# main_V3.net
KiCad netlist of a schematic drawn in EAGLE
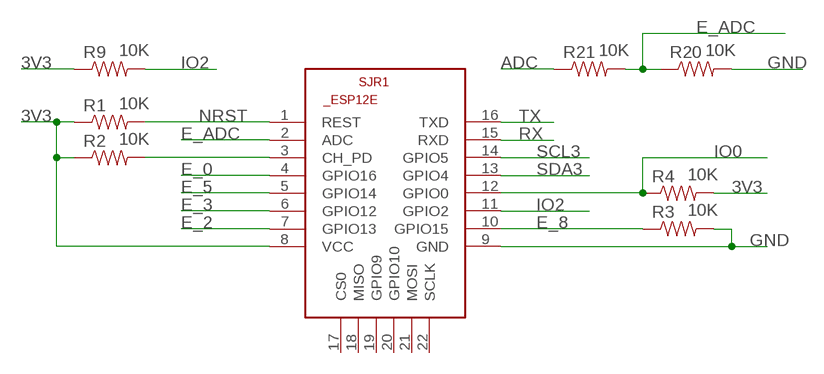
[diagram p0: schematic, sheet 1]
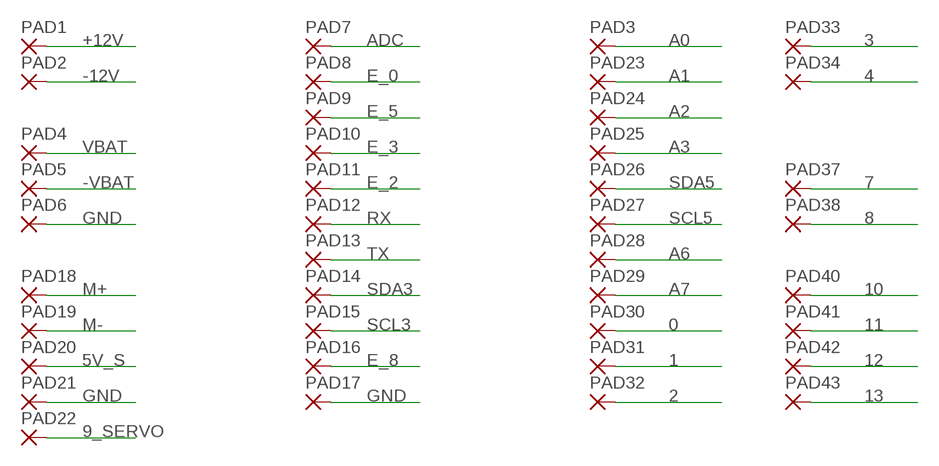
[diagram p1: schematic, sheet 2]
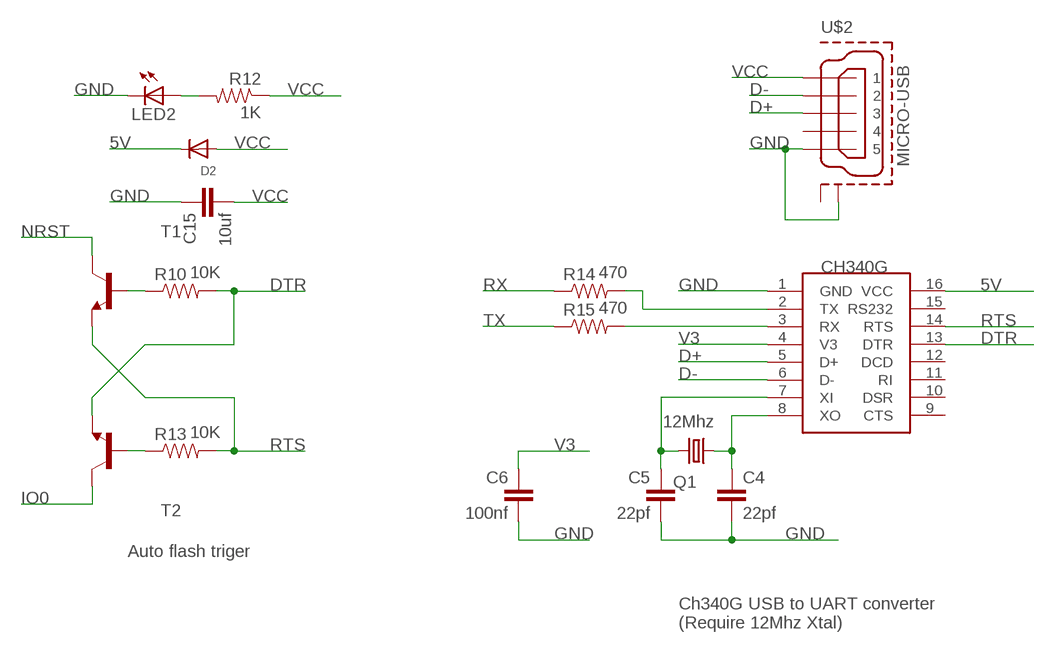
[diagram p2: schematic, sheet 3]
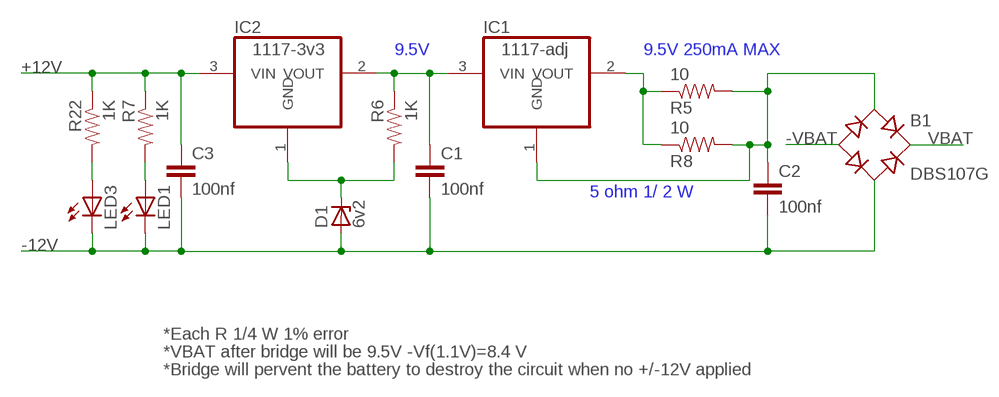
[diagram p3: schematic, sheet 4]
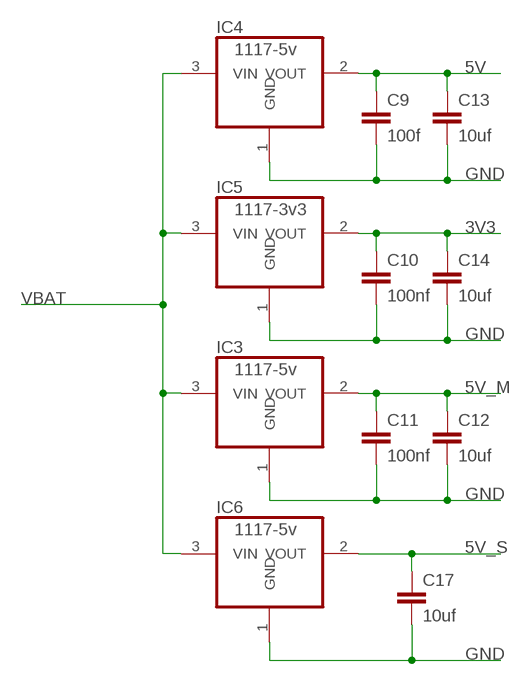
[diagram p4: schematic, sheet 5]
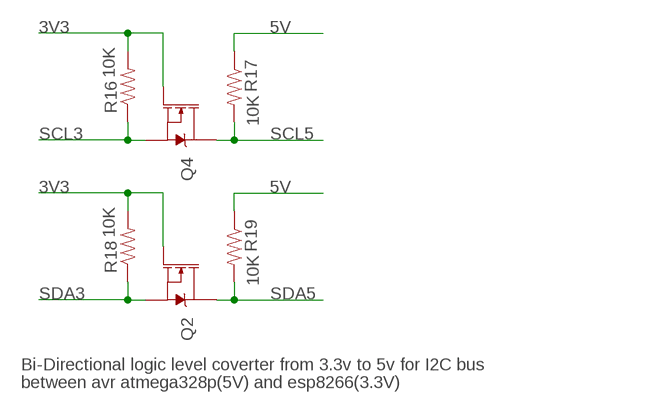
[diagram p5: schematic, sheet 6]
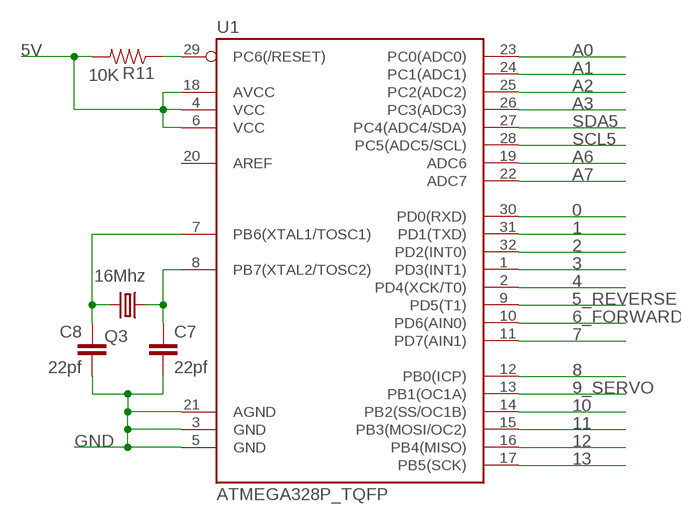
[diagram p6: schematic, sheet 7]
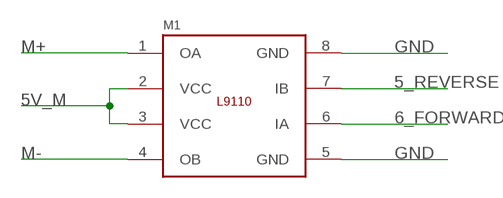
[diagram p7: schematic, sheet 8]

(export (version "E")
  (design (tool "Eeschema 10.0.6"))
  (components
    (comp (ref "Q2")
      (value "MOSFET-NCH-BSS138")
      (footprint "eagle-import:SOT23-3")
      (libsource (lib "eagle-import") (part "MOSFET-NCH-BSS138"))
    )
    (comp (ref "Q4")
      (value "MOSFET-NCH-BSS138")
      (footprint "eagle-import:SOT23-3")
      (libsource (lib "eagle-import") (part "MOSFET-NCH-BSS138"))
    )
    (comp (ref "R16")
      (value "10K")
      (footprint "eagle-import:1206")
      (libsource (lib "eagle-import") (part "RESISTOR1206"))
    )
    (comp (ref "R17")
      (value "10K")
      (footprint "eagle-import:1206")
      (libsource (lib "eagle-import") (part "RESISTOR1206"))
    )
    (comp (ref "R18")
      (value "10K")
      (footprint "eagle-import:1206")
      (libsource (lib "eagle-import") (part "RESISTOR1206"))
    )
    (comp (ref "R19")
      (value "10K")
      (footprint "eagle-import:1206")
      (libsource (lib "eagle-import") (part "RESISTOR1206"))
    )
    (comp (ref "B1")
      (value "DBS107G")
      (footprint "eagle-import:DBS")
      (libsource (lib "eagle-import") (part "DB?GS107"))
    )
    (comp (ref "C1")
      (value "100nf")
      (footprint "eagle-import:C1206K")
      (libsource (lib "eagle-import") (part "C-EUC1206K"))
    )
    (comp (ref "C2")
      (value "100nf")
      (footprint "eagle-import:C1206K")
      (libsource (lib "eagle-import") (part "C-EUC1206K"))
    )
    (comp (ref "C3")
      (value "100nf")
      (footprint "eagle-import:C1206K")
      (libsource (lib "eagle-import") (part "C-EUC1206K"))
    )
    (comp (ref "D1")
      (value "6v2")
      (footprint "eagle-import:SOT23")
      (libsource (lib "eagle-import") (part "ZENER-DIODESOT23"))
    )
    (comp (ref "IC1")
      (value "1117-adj")
      (footprint "eagle-import:SOT223")
      (fields (field (name "MPN") "REG1117"))
      (libsource (lib "eagle-import") (part "REG1117"))
    )
    (comp (ref "IC2")
      (value "1117-3v3")
      (footprint "eagle-import:SOT223")
      (fields (field (name "MPN") "REG1117"))
      (libsource (lib "eagle-import") (part "REG1117"))
    )
    (comp (ref "LED1")
      (value "LEDSMT1206")
      (footprint "eagle-import:1206")
      (libsource (lib "eagle-import") (part "LEDSMT1206"))
    )
    (comp (ref "LED3")
      (value "LEDSMT1206")
      (footprint "eagle-import:1206")
      (libsource (lib "eagle-import") (part "LEDSMT1206"))
    )
    (comp (ref "R5")
      (value "10")
      (footprint "eagle-import:1206")
      (libsource (lib "eagle-import") (part "RESISTOR1206"))
    )
    (comp (ref "R6")
      (value "1K")
      (footprint "eagle-import:1206")
      (libsource (lib "eagle-import") (part "RESISTOR1206"))
    )
    (comp (ref "R7")
      (value "1K")
      (footprint "eagle-import:1206")
      (libsource (lib "eagle-import") (part "RESISTOR1206"))
    )
    (comp (ref "R8")
      (value "10")
      (footprint "eagle-import:1206")
      (libsource (lib "eagle-import") (part "RESISTOR1206"))
    )
    (comp (ref "R22")
      (value "1K")
      (footprint "eagle-import:1206")
      (libsource (lib "eagle-import") (part "RESISTOR1206"))
    )
    (comp (ref "PAD1")
      (value "WIREPADSMD5-2,5")
      (footprint "eagle-import:5-2,5")
      (libsource (lib "eagle-import") (part "WIREPADSMD5-2,5"))
    )
    (comp (ref "PAD2")
      (value "WIREPADSMD5-2,5")
      (footprint "eagle-import:5-2,5")
      (libsource (lib "eagle-import") (part "WIREPADSMD5-2,5"))
    )
    (comp (ref "PAD3")
      (value "WIREPADSMD1,27-254")
      (footprint "eagle-import:SMD1,27-2,54")
      (libsource (lib "eagle-import") (part "WIREPADSMD1,27-254"))
    )
    (comp (ref "PAD4")
      (value "WIREPADSMD5-2,5")
      (footprint "eagle-import:5-2,5")
      (libsource (lib "eagle-import") (part "WIREPADSMD5-2,5"))
    )
    (comp (ref "PAD5")
      (value "WIREPADSMD5-2,5")
      (footprint "eagle-import:5-2,5")
      (libsource (lib "eagle-import") (part "WIREPADSMD5-2,5"))
    )
    (comp (ref "PAD6")
      (value "WIREPADSMD5-2,5")
      (footprint "eagle-import:5-2,5")
      (libsource (lib "eagle-import") (part "WIREPADSMD5-2,5"))
    )
    (comp (ref "PAD7")
      (value "WIREPADSMD1,27-254")
      (footprint "eagle-import:SMD1,27-2,54")
      (libsource (lib "eagle-import") (part "WIREPADSMD1,27-254"))
    )
    (comp (ref "PAD8")
      (value "WIREPADSMD1,27-254")
      (footprint "eagle-import:SMD1,27-2,54")
      (libsource (lib "eagle-import") (part "WIREPADSMD1,27-254"))
    )
    (comp (ref "PAD9")
      (value "WIREPADSMD1,27-254")
      (footprint "eagle-import:SMD1,27-2,54")
      (libsource (lib "eagle-import") (part "WIREPADSMD1,27-254"))
    )
    (comp (ref "PAD10")
      (value "WIREPADSMD1,27-254")
      (footprint "eagle-import:SMD1,27-2,54")
      (libsource (lib "eagle-import") (part "WIREPADSMD1,27-254"))
    )
    (comp (ref "PAD11")
      (value "WIREPADSMD1,27-254")
      (footprint "eagle-import:SMD1,27-2,54")
      (libsource (lib "eagle-import") (part "WIREPADSMD1,27-254"))
    )
    (comp (ref "PAD12")
      (value "WIREPADSMD1,27-254")
      (footprint "eagle-import:SMD1,27-2,54")
      (libsource (lib "eagle-import") (part "WIREPADSMD1,27-254"))
    )
    (comp (ref "PAD13")
      (value "WIREPADSMD1,27-254")
      (footprint "eagle-import:SMD1,27-2,54")
      (libsource (lib "eagle-import") (part "WIREPADSMD1,27-254"))
    )
    (comp (ref "PAD14")
      (value "WIREPADSMD1,27-254")
      (footprint "eagle-import:SMD1,27-2,54")
      (libsource (lib "eagle-import") (part "WIREPADSMD1,27-254"))
    )
    (comp (ref "PAD15")
      (value "WIREPADSMD1,27-254")
      (footprint "eagle-import:SMD1,27-2,54")
      (libsource (lib "eagle-import") (part "WIREPADSMD1,27-254"))
    )
    (comp (ref "PAD16")
      (value "WIREPADSMD1,27-254")
      (footprint "eagle-import:SMD1,27-2,54")
      (libsource (lib "eagle-import") (part "WIREPADSMD1,27-254"))
    )
    (comp (ref "PAD17")
      (value "WIREPADSMD1,27-254")
      (footprint "eagle-import:SMD1,27-2,54")
      (libsource (lib "eagle-import") (part "WIREPADSMD1,27-254"))
    )
    (comp (ref "PAD18")
      (value "WIREPADSMD1,27-254")
      (footprint "eagle-import:SMD1,27-2,54")
      (libsource (lib "eagle-import") (part "WIREPADSMD1,27-254"))
    )
    (comp (ref "PAD19")
      (value "WIREPADSMD1,27-254")
      (footprint "eagle-import:SMD1,27-2,54")
      (libsource (lib "eagle-import") (part "WIREPADSMD1,27-254"))
    )
    (comp (ref "PAD20")
      (value "WIREPADSMD1,27-254")
      (footprint "eagle-import:SMD1,27-2,54")
      (libsource (lib "eagle-import") (part "WIREPADSMD1,27-254"))
    )
    (comp (ref "PAD21")
      (value "WIREPADSMD1,27-254")
      (footprint "eagle-import:SMD1,27-2,54")
      (libsource (lib "eagle-import") (part "WIREPADSMD1,27-254"))
    )
    (comp (ref "PAD22")
      (value "WIREPADSMD1,27-254")
      (footprint "eagle-import:SMD1,27-2,54")
      (libsource (lib "eagle-import") (part "WIREPADSMD1,27-254"))
    )
    (comp (ref "PAD23")
      (value "WIREPADSMD1,27-254")
      (footprint "eagle-import:SMD1,27-2,54")
      (libsource (lib "eagle-import") (part "WIREPADSMD1,27-254"))
    )
    (comp (ref "PAD24")
      (value "WIREPADSMD1,27-254")
      (footprint "eagle-import:SMD1,27-2,54")
      (libsource (lib "eagle-import") (part "WIREPADSMD1,27-254"))
    )
    (comp (ref "PAD25")
      (value "WIREPADSMD1,27-254")
      (footprint "eagle-import:SMD1,27-2,54")
      (libsource (lib "eagle-import") (part "WIREPADSMD1,27-254"))
    )
    (comp (ref "PAD26")
      (value "WIREPADSMD1,27-254")
      (footprint "eagle-import:SMD1,27-2,54")
      (libsource (lib "eagle-import") (part "WIREPADSMD1,27-254"))
    )
    (comp (ref "PAD27")
      (value "WIREPADSMD1,27-254")
      (footprint "eagle-import:SMD1,27-2,54")
      (libsource (lib "eagle-import") (part "WIREPADSMD1,27-254"))
    )
    (comp (ref "PAD28")
      (value "WIREPADSMD1,27-254")
      (footprint "eagle-import:SMD1,27-2,54")
      (libsource (lib "eagle-import") (part "WIREPADSMD1,27-254"))
    )
    (comp (ref "PAD29")
      (value "WIREPADSMD1,27-254")
      (footprint "eagle-import:SMD1,27-2,54")
      (libsource (lib "eagle-import") (part "WIREPADSMD1,27-254"))
    )
    (comp (ref "PAD30")
      (value "WIREPADSMD1,27-254")
      (footprint "eagle-import:SMD1,27-2,54")
      (libsource (lib "eagle-import") (part "WIREPADSMD1,27-254"))
    )
    (comp (ref "PAD31")
      (value "WIREPADSMD1,27-254")
      (footprint "eagle-import:SMD1,27-2,54")
      (libsource (lib "eagle-import") (part "WIREPADSMD1,27-254"))
    )
    (comp (ref "PAD32")
      (value "WIREPADSMD1,27-254")
      (footprint "eagle-import:SMD1,27-2,54")
      (libsource (lib "eagle-import") (part "WIREPADSMD1,27-254"))
    )
    (comp (ref "PAD33")
      (value "WIREPADSMD1,27-254")
      (footprint "eagle-import:SMD1,27-2,54")
      (libsource (lib "eagle-import") (part "WIREPADSMD1,27-254"))
    )
    (comp (ref "PAD34")
      (value "WIREPADSMD1,27-254")
      (footprint "eagle-import:SMD1,27-2,54")
      (libsource (lib "eagle-import") (part "WIREPADSMD1,27-254"))
    )
    (comp (ref "PAD37")
      (value "WIREPADSMD1,27-254")
      (footprint "eagle-import:SMD1,27-2,54")
      (libsource (lib "eagle-import") (part "WIREPADSMD1,27-254"))
    )
    (comp (ref "PAD38")
      (value "WIREPADSMD1,27-254")
      (footprint "eagle-import:SMD1,27-2,54")
      (libsource (lib "eagle-import") (part "WIREPADSMD1,27-254"))
    )
    (comp (ref "PAD40")
      (value "WIREPADSMD1,27-254")
      (footprint "eagle-import:SMD1,27-2,54")
      (libsource (lib "eagle-import") (part "WIREPADSMD1,27-254"))
    )
    (comp (ref "PAD41")
      (value "WIREPADSMD1,27-254")
      (footprint "eagle-import:SMD1,27-2,54")
      (libsource (lib "eagle-import") (part "WIREPADSMD1,27-254"))
    )
    (comp (ref "PAD42")
      (value "WIREPADSMD1,27-254")
      (footprint "eagle-import:SMD1,27-2,54")
      (libsource (lib "eagle-import") (part "WIREPADSMD1,27-254"))
    )
    (comp (ref "PAD43")
      (value "WIREPADSMD1,27-254")
      (footprint "eagle-import:SMD1,27-2,54")
      (libsource (lib "eagle-import") (part "WIREPADSMD1,27-254"))
    )
    (comp (ref "M1")
      (value "L9110")
      (footprint "eagle-import:SO8P")
      (libsource (lib "eagle-import") (part "L9110"))
    )
    (comp (ref "C9")
      (value "100f")
      (footprint "eagle-import:C1206K")
      (libsource (lib "eagle-import") (part "C-EUC1206K"))
    )
    (comp (ref "C10")
      (value "100nf")
      (footprint "eagle-import:C1206K")
      (libsource (lib "eagle-import") (part "C-EUC1206K"))
    )
    (comp (ref "C11")
      (value "100nf")
      (footprint "eagle-import:C1206K")
      (libsource (lib "eagle-import") (part "C-EUC1206K"))
    )
    (comp (ref "C12")
      (value "10uf")
      (footprint "eagle-import:C1206K")
      (libsource (lib "eagle-import") (part "C-EUC1206K"))
    )
    (comp (ref "C13")
      (value "10uf")
      (footprint "eagle-import:C1206K")
      (libsource (lib "eagle-import") (part "C-EUC1206K"))
    )
    (comp (ref "C14")
      (value "10uf")
      (footprint "eagle-import:C1206K")
      (libsource (lib "eagle-import") (part "C-EUC1206K"))
    )
    (comp (ref "C17")
      (value "10uf")
      (footprint "eagle-import:C1206K")
      (libsource (lib "eagle-import") (part "C-EUC1206K"))
    )
    (comp (ref "IC3")
      (value "1117-5v")
      (footprint "eagle-import:SOT223")
      (fields (field (name "MPN") "REG1117"))
      (libsource (lib "eagle-import") (part "REG1117"))
    )
    (comp (ref "IC4")
      (value "1117-5v")
      (footprint "eagle-import:SOT223")
      (fields (field (name "MPN") "REG1117"))
      (libsource (lib "eagle-import") (part "REG1117"))
    )
    (comp (ref "IC5")
      (value "1117-3v3")
      (footprint "eagle-import:SOT223")
      (fields (field (name "MPN") "REG1117"))
      (libsource (lib "eagle-import") (part "REG1117"))
    )
    (comp (ref "IC6")
      (value "1117-5v")
      (footprint "eagle-import:SOT223")
      (fields (field (name "MPN") "REG1117"))
      (libsource (lib "eagle-import") (part "REG1117"))
    )
    (comp (ref "C7")
      (value "22pf")
      (footprint "eagle-import:C1206K")
      (libsource (lib "eagle-import") (part "C-EUC1206K"))
    )
    (comp (ref "C8")
      (value "22pf")
      (footprint "eagle-import:C1206K")
      (libsource (lib "eagle-import") (part "C-EUC1206K"))
    )
    (comp (ref "Q3")
      (value "16Mhz")
      (footprint "eagle-import:CSM-7X-DU")
      (libsource (lib "eagle-import") (part "CSM-7X-DU"))
    )
    (comp (ref "R11")
      (value "10K")
      (footprint "eagle-import:1206")
      (libsource (lib "eagle-import") (part "RESISTOR1206"))
    )
    (comp (ref "U1")
      (value "ATMEGA328P_TQFP")
      (footprint "eagle-import:TQFP32-08")
      (libsource (lib "eagle-import") (part "ATMEGA328P_TQFP"))
    )
    (comp (ref "C4")
      (value "22pf")
      (footprint "eagle-import:C1206K")
      (libsource (lib "eagle-import") (part "C-EUC1206K"))
    )
    (comp (ref "C5")
      (value "22pf")
      (footprint "eagle-import:C1206K")
      (libsource (lib "eagle-import") (part "C-EUC1206K"))
    )
    (comp (ref "C6")
      (value "100nf")
      (footprint "eagle-import:C1206K")
      (libsource (lib "eagle-import") (part "C-EUC1206K"))
    )
    (comp (ref "C15")
      (value "10uf")
      (footprint "eagle-import:C1206K")
      (libsource (lib "eagle-import") (part "C-EUC1206K"))
    )
    (comp (ref "D2")
      (value "DIODESMA")
      (footprint "eagle-import:SMADIODE")
      (libsource (lib "eagle-import") (part "DIODESMA"))
    )
    (comp (ref "LED2")
      (value "LEDSMT1206")
      (footprint "eagle-import:1206")
      (libsource (lib "eagle-import") (part "LEDSMT1206"))
    )
    (comp (ref "Q1")
      (value "12Mhz")
      (footprint "eagle-import:CSM-7X-DU")
      (libsource (lib "eagle-import") (part "CSM-7X-DU"))
    )
    (comp (ref "R10")
      (value "10K")
      (footprint "eagle-import:1206")
      (libsource (lib "eagle-import") (part "RESISTOR1206"))
    )
    (comp (ref "R12")
      (value "1K")
      (footprint "eagle-import:1206")
      (libsource (lib "eagle-import") (part "RESISTOR1206"))
    )
    (comp (ref "R13")
      (value "10K")
      (footprint "eagle-import:1206")
      (libsource (lib "eagle-import") (part "RESISTOR1206"))
    )
    (comp (ref "R14")
      (value "470")
      (footprint "eagle-import:1206")
      (libsource (lib "eagle-import") (part "RESISTOR1206"))
    )
    (comp (ref "R15")
      (value "470")
      (footprint "eagle-import:1206")
      (libsource (lib "eagle-import") (part "RESISTOR1206"))
    )
    (comp (ref "T1")
      (value "MMBT5551LT1-NPN-SOT23-BEC")
      (footprint "eagle-import:SOT23-BEC")
      (libsource (lib "eagle-import") (part "-NPN-SOT23-BECMMBT5551LT1"))
    )
    (comp (ref "T2")
      (value "MMBT5551LT1-NPN-SOT23-BEC")
      (footprint "eagle-import:SOT23-BEC")
      (libsource (lib "eagle-import") (part "-NPN-SOT23-BECMMBT5551LT1"))
    )
    (comp (ref "U$1")
      (value "CH340G")
      (footprint "eagle-import:SOIC16")
      (libsource (lib "eagle-import") (part "CH340G"))
    )
    (comp (ref "U$2")
      (value "MICRO-USB")
      (footprint "eagle-import:47589-0001")
      (libsource (lib "eagle-import") (part "MICRO-USB-RECEPTACLE47589-0001"))
    )
    (comp (ref "R1")
      (value "10K")
      (footprint "eagle-import:1206")
      (libsource (lib "eagle-import") (part "RESISTOR1206"))
    )
    (comp (ref "R2")
      (value "10K")
      (footprint "eagle-import:1206")
      (libsource (lib "eagle-import") (part "RESISTOR1206"))
    )
    (comp (ref "R3")
      (value "10K")
      (footprint "eagle-import:1206")
      (libsource (lib "eagle-import") (part "RESISTOR1206"))
    )
    (comp (ref "R4")
      (value "10K")
      (footprint "eagle-import:1206")
      (libsource (lib "eagle-import") (part "RESISTOR1206"))
    )
    (comp (ref "R9")
      (value "10K")
      (footprint "eagle-import:1206")
      (libsource (lib "eagle-import") (part "RESISTOR1206"))
    )
    (comp (ref "R20")
      (value "10K")
      (footprint "eagle-import:1206")
      (libsource (lib "eagle-import") (part "RESISTOR1206"))
    )
    (comp (ref "R21")
      (value "10K")
      (footprint "eagle-import:1206")
      (libsource (lib "eagle-import") (part "RESISTOR1206"))
    )
    (comp (ref "SJR1")
      (value "ESP8266-12EESP12E")
      (footprint "eagle-import:ESP8266-ESP12E")
      (libsource (lib "eagle-import") (part "ESP8266-12EESP12E"))
    )
  )
  (nets
    (net (code "1") (name "+12V") (class "Default")
      (node (ref "C3") (pin "1") (pinfunction "1_1") (pintype "passive"))
      (node (ref "IC2") (pin "3") (pinfunction "VIN_3") (pintype "input"))
      (node (ref "PAD1") (pin "1") (pinfunction "P_1") (pintype "passive"))
      (node (ref "R22") (pin "1") (pinfunction "1_1") (pintype "passive"))
      (node (ref "R7") (pin "1") (pinfunction "1_1") (pintype "passive"))
    )
    (net (code "2") (name "-12V") (class "Default")
      (node (ref "B1") (pin "AC2") (pinfunction "AC2_AC2") (pintype "passive"))
      (node (ref "C1") (pin "2") (pinfunction "2_2") (pintype "passive"))
      (node (ref "C2") (pin "2") (pinfunction "2_2") (pintype "passive"))
      (node (ref "C3") (pin "2") (pinfunction "2_2") (pintype "passive"))
      (node (ref "D1") (pin "1") (pinfunction "A_1") (pintype "passive"))
      (node (ref "LED1") (pin "C") (pinfunction "C_C") (pintype "passive"))
      (node (ref "LED3") (pin "C") (pinfunction "C_C") (pintype "passive"))
      (node (ref "PAD2") (pin "1") (pinfunction "P_1") (pintype "passive"))
    )
    (net (code "3") (name "-VBAT") (class "Default")
      (node (ref "B1") (pin "-") (pinfunction "-_-") (pintype "passive"))
      (node (ref "PAD5") (pin "1") (pinfunction "P_1") (pintype "passive"))
    )
    (net (code "4") (name "0") (class "Default")
      (node (ref "PAD30") (pin "1") (pinfunction "P_1") (pintype "passive"))
      (node (ref "U1") (pin "30") (pinfunction "PD0(RXD)_30") (pintype "bidirectional"))
    )
    (net (code "5") (name "1") (class "Default")
      (node (ref "PAD31") (pin "1") (pinfunction "P_1") (pintype "passive"))
      (node (ref "U1") (pin "31") (pinfunction "PD1(TXD)_31") (pintype "bidirectional"))
    )
    (net (code "6") (name "2") (class "Default")
      (node (ref "PAD32") (pin "1") (pinfunction "P_1") (pintype "passive"))
      (node (ref "U1") (pin "32") (pinfunction "PD2(INT0)_32") (pintype "bidirectional"))
    )
    (net (code "7") (name "3") (class "Default")
      (node (ref "PAD33") (pin "1") (pinfunction "P_1") (pintype "passive"))
      (node (ref "U1") (pin "1") (pinfunction "PD3(INT1)_1") (pintype "bidirectional"))
    )
    (net (code "8") (name "3V3") (class "Default")
      (node (ref "C10") (pin "1") (pinfunction "1_1") (pintype "passive"))
      (node (ref "C14") (pin "1") (pinfunction "1_1") (pintype "passive"))
      (node (ref "IC5") (pin "2") (pinfunction "VOUT_2") (pintype "output"))
      (node (ref "Q2") (pin "1") (pinfunction "G_1") (pintype "bidirectional"))
      (node (ref "Q4") (pin "1") (pinfunction "G_1") (pintype "bidirectional"))
      (node (ref "R1") (pin "1") (pinfunction "1_1") (pintype "passive"))
      (node (ref "R16") (pin "2") (pinfunction "2_2") (pintype "passive"))
      (node (ref "R18") (pin "2") (pinfunction "2_2") (pintype "passive"))
      (node (ref "R2") (pin "1") (pinfunction "1_1") (pintype "passive"))
      (node (ref "R4") (pin "2") (pinfunction "2_2") (pintype "passive"))
      (node (ref "R9") (pin "1") (pinfunction "1_1") (pintype "passive"))
      (node (ref "SJR1") (pin "8") (pinfunction "VCC_8") (pintype "bidirectional"))
    )
    (net (code "9") (name "4") (class "Default")
      (node (ref "PAD34") (pin "1") (pinfunction "P_1") (pintype "passive"))
      (node (ref "U1") (pin "2") (pinfunction "PD4(XCK/T0)_2") (pintype "bidirectional"))
    )
    (net (code "10") (name "5V") (class "Default")
      (node (ref "C13") (pin "1") (pinfunction "1_1") (pintype "passive"))
      (node (ref "C9") (pin "1") (pinfunction "1_1") (pintype "passive"))
      (node (ref "D2") (pin "C") (pinfunction "C_C") (pintype "passive"))
      (node (ref "IC4") (pin "2") (pinfunction "VOUT_2") (pintype "output"))
      (node (ref "R11") (pin "2") (pinfunction "2_2") (pintype "passive"))
      (node (ref "R17") (pin "1") (pinfunction "1_1") (pintype "passive"))
      (node (ref "R19") (pin "1") (pinfunction "1_1") (pintype "passive"))
      (node (ref "U$1") (pin "16") (pinfunction "VCC_16") (pintype "bidirectional"))
      (node (ref "U1") (pin "18") (pinfunction "AVCC_18") (pintype "bidirectional"))
      (node (ref "U1") (pin "4") (pinfunction "VCC_4") (pintype "bidirectional"))
      (node (ref "U1") (pin "6") (pinfunction "VCC_6") (pintype "bidirectional"))
    )
    (net (code "11") (name "5V_M") (class "Default")
      (node (ref "C11") (pin "1") (pinfunction "1_1") (pintype "passive"))
      (node (ref "C12") (pin "1") (pinfunction "1_1") (pintype "passive"))
      (node (ref "IC3") (pin "2") (pinfunction "VOUT_2") (pintype "output"))
      (node (ref "M1") (pin "2") (pinfunction "VCC_2") (pintype "bidirectional"))
      (node (ref "M1") (pin "3") (pinfunction "VCC_3") (pintype "bidirectional"))
    )
    (net (code "12") (name "5V_S") (class "Default")
      (node (ref "C17") (pin "1") (pinfunction "1_1") (pintype "passive"))
      (node (ref "IC6") (pin "2") (pinfunction "VOUT_2") (pintype "output"))
      (node (ref "PAD20") (pin "1") (pinfunction "P_1") (pintype "passive"))
    )
    (net (code "13") (name "5_REVERSE") (class "Default")
      (node (ref "M1") (pin "7") (pinfunction "IB_7") (pintype "bidirectional"))
      (node (ref "U1") (pin "9") (pinfunction "PD5(T1)_9") (pintype "bidirectional"))
    )
    (net (code "14") (name "6_FORWARD") (class "Default")
      (node (ref "M1") (pin "6") (pinfunction "IA_6") (pintype "bidirectional"))
      (node (ref "U1") (pin "10") (pinfunction "PD6(AIN0)_10") (pintype "bidirectional"))
    )
    (net (code "15") (name "7") (class "Default")
      (node (ref "PAD37") (pin "1") (pinfunction "P_1") (pintype "passive"))
      (node (ref "U1") (pin "11") (pinfunction "PD7(AIN1)_11") (pintype "bidirectional"))
    )
    (net (code "16") (name "8") (class "Default")
      (node (ref "PAD38") (pin "1") (pinfunction "P_1") (pintype "passive"))
      (node (ref "U1") (pin "12") (pinfunction "PB0(ICP)_12") (pintype "bidirectional"))
    )
    (net (code "17") (name "9_SERVO") (class "Default")
      (node (ref "PAD22") (pin "1") (pinfunction "P_1") (pintype "passive"))
      (node (ref "U1") (pin "13") (pinfunction "PB1(OC1A)_13") (pintype "bidirectional"))
    )
    (net (code "18") (name "10") (class "Default")
      (node (ref "PAD40") (pin "1") (pinfunction "P_1") (pintype "passive"))
      (node (ref "U1") (pin "14") (pinfunction "PB2(SS/OC1B)_14") (pintype "bidirectional"))
    )
    (net (code "19") (name "11") (class "Default")
      (node (ref "PAD41") (pin "1") (pinfunction "P_1") (pintype "passive"))
      (node (ref "U1") (pin "15") (pinfunction "PB3(MOSI/OC2)_15") (pintype "bidirectional"))
    )
    (net (code "20") (name "12") (class "Default")
      (node (ref "PAD42") (pin "1") (pinfunction "P_1") (pintype "passive"))
      (node (ref "U1") (pin "16") (pinfunction "PB4(MISO)_16") (pintype "bidirectional"))
    )
    (net (code "21") (name "13") (class "Default")
      (node (ref "PAD43") (pin "1") (pinfunction "P_1") (pintype "passive"))
      (node (ref "U1") (pin "17") (pinfunction "PB5(SCK)_17") (pintype "bidirectional"))
    )
    (net (code "22") (name "A0") (class "Default")
      (node (ref "PAD3") (pin "1") (pinfunction "P_1") (pintype "passive"))
      (node (ref "U1") (pin "23") (pinfunction "PC0(ADC0)_23") (pintype "bidirectional"))
    )
    (net (code "23") (name "A1") (class "Default")
      (node (ref "PAD23") (pin "1") (pinfunction "P_1") (pintype "passive"))
      (node (ref "U1") (pin "24") (pinfunction "PC1(ADC1)_24") (pintype "bidirectional"))
    )
    (net (code "24") (name "A2") (class "Default")
      (node (ref "PAD24") (pin "1") (pinfunction "P_1") (pintype "passive"))
      (node (ref "U1") (pin "25") (pinfunction "PC2(ADC2)_25") (pintype "bidirectional"))
    )
    (net (code "25") (name "A3") (class "Default")
      (node (ref "PAD25") (pin "1") (pinfunction "P_1") (pintype "passive"))
      (node (ref "U1") (pin "26") (pinfunction "PC3(ADC3)_26") (pintype "bidirectional"))
    )
    (net (code "26") (name "A6") (class "Default")
      (node (ref "PAD28") (pin "1") (pinfunction "P_1") (pintype "passive"))
      (node (ref "U1") (pin "19") (pinfunction "ADC6_19") (pintype "bidirectional"))
    )
    (net (code "27") (name "A7") (class "Default")
      (node (ref "PAD29") (pin "1") (pinfunction "P_1") (pintype "passive"))
      (node (ref "U1") (pin "22") (pinfunction "ADC7_22") (pintype "bidirectional"))
    )
    (net (code "28") (name "ADC") (class "Default")
      (node (ref "PAD7") (pin "1") (pinfunction "P_1") (pintype "passive"))
      (node (ref "R21") (pin "1") (pinfunction "1_1") (pintype "passive"))
    )
    (net (code "29") (name "D+") (class "Default")
      (node (ref "U$1") (pin "5") (pinfunction "D+_5") (pintype "bidirectional"))
      (node (ref "U$2") (pin "3") (pinfunction "3_3") (pintype "input"))
    )
    (net (code "30") (name "D-") (class "Default")
      (node (ref "U$1") (pin "6") (pinfunction "D-_6") (pintype "bidirectional"))
      (node (ref "U$2") (pin "2") (pinfunction "2_2") (pintype "input"))
    )
    (net (code "31") (name "DTR") (class "Default")
      (node (ref "R10") (pin "2") (pinfunction "2_2") (pintype "passive"))
      (node (ref "T2") (pin "E") (pinfunction "E_E") (pintype "passive"))
      (node (ref "U$1") (pin "13") (pinfunction "DTR_13") (pintype "bidirectional"))
    )
    (net (code "32") (name "E_0") (class "Default")
      (node (ref "PAD8") (pin "1") (pinfunction "P_1") (pintype "passive"))
      (node (ref "SJR1") (pin "4") (pinfunction "GPIO16_4") (pintype "bidirectional"))
    )
    (net (code "33") (name "E_2") (class "Default")
      (node (ref "PAD11") (pin "1") (pinfunction "P_1") (pintype "passive"))
      (node (ref "SJR1") (pin "7") (pinfunction "GPIO13_7") (pintype "bidirectional"))
    )
    (net (code "34") (name "E_3") (class "Default")
      (node (ref "PAD10") (pin "1") (pinfunction "P_1") (pintype "passive"))
      (node (ref "SJR1") (pin "6") (pinfunction "GPIO12_6") (pintype "bidirectional"))
    )
    (net (code "35") (name "E_5") (class "Default")
      (node (ref "PAD9") (pin "1") (pinfunction "P_1") (pintype "passive"))
      (node (ref "SJR1") (pin "5") (pinfunction "GPIO14_5") (pintype "bidirectional"))
    )
    (net (code "36") (name "E_8") (class "Default")
      (node (ref "PAD16") (pin "1") (pinfunction "P_1") (pintype "passive"))
      (node (ref "R3") (pin "1") (pinfunction "1_1") (pintype "passive"))
      (node (ref "SJR1") (pin "10") (pinfunction "GPIO15_10") (pintype "bidirectional"))
    )
    (net (code "37") (name "E_ADC") (class "Default")
      (node (ref "R20") (pin "1") (pinfunction "1_1") (pintype "passive"))
      (node (ref "R21") (pin "2") (pinfunction "2_2") (pintype "passive"))
      (node (ref "SJR1") (pin "2") (pinfunction "ADC_2") (pintype "bidirectional"))
    )
    (net (code "38") (name "GND") (class "Default")
      (node (ref "C10") (pin "2") (pinfunction "2_2") (pintype "passive"))
      (node (ref "C11") (pin "2") (pinfunction "2_2") (pintype "passive"))
      (node (ref "C12") (pin "2") (pinfunction "2_2") (pintype "passive"))
      (node (ref "C13") (pin "2") (pinfunction "2_2") (pintype "passive"))
      (node (ref "C14") (pin "2") (pinfunction "2_2") (pintype "passive"))
      (node (ref "C15") (pin "1") (pinfunction "1_1") (pintype "passive"))
      (node (ref "C17") (pin "2") (pinfunction "2_2") (pintype "passive"))
      (node (ref "C4") (pin "2") (pinfunction "2_2") (pintype "passive"))
      (node (ref "C5") (pin "2") (pinfunction "2_2") (pintype "passive"))
      (node (ref "C6") (pin "2") (pinfunction "2_2") (pintype "passive"))
      (node (ref "C7") (pin "2") (pinfunction "2_2") (pintype "passive"))
      (node (ref "C8") (pin "2") (pinfunction "2_2") (pintype "passive"))
      (node (ref "C9") (pin "2") (pinfunction "2_2") (pintype "passive"))
      (node (ref "IC3") (pin "1") (pinfunction "GND_1") (pintype "power_in"))
      (node (ref "IC4") (pin "1") (pinfunction "GND_1") (pintype "power_in"))
      (node (ref "IC5") (pin "1") (pinfunction "GND_1") (pintype "power_in"))
      (node (ref "IC6") (pin "1") (pinfunction "GND_1") (pintype "power_in"))
      (node (ref "LED2") (pin "C") (pinfunction "C_C") (pintype "passive"))
      (node (ref "M1") (pin "5") (pinfunction "GND_5") (pintype "bidirectional"))
      (node (ref "M1") (pin "8") (pinfunction "GND_8") (pintype "bidirectional"))
      (node (ref "PAD17") (pin "1") (pinfunction "P_1") (pintype "passive"))
      (node (ref "PAD21") (pin "1") (pinfunction "P_1") (pintype "passive"))
      (node (ref "PAD6") (pin "1") (pinfunction "P_1") (pintype "passive"))
      (node (ref "R20") (pin "2") (pinfunction "2_2") (pintype "passive"))
      (node (ref "R3") (pin "2") (pinfunction "2_2") (pintype "passive"))
      (node (ref "SJR1") (pin "9") (pinfunction "GND_9") (pintype "bidirectional"))
      (node (ref "U$1") (pin "1") (pinfunction "GND_1") (pintype "bidirectional"))
      (node (ref "U$2") (pin "5") (pinfunction "5_5") (pintype "input"))
      (node (ref "U$2") (pin "P$2") (pinfunction "GND2_P$2") (pintype "bidirectional"))
      (node (ref "U1") (pin "21") (pinfunction "AGND_21") (pintype "bidirectional"))
      (node (ref "U1") (pin "3") (pinfunction "GND_3") (pintype "bidirectional"))
      (node (ref "U1") (pin "5") (pinfunction "GND_5") (pintype "bidirectional"))
    )
    (net (code "39") (name "IO0") (class "Default")
      (node (ref "R4") (pin "1") (pinfunction "1_1") (pintype "passive"))
      (node (ref "SJR1") (pin "12") (pinfunction "GPIO0_12") (pintype "bidirectional"))
      (node (ref "T2") (pin "C") (pinfunction "C_C") (pintype "passive"))
    )
    (net (code "40") (name "IO2") (class "Default")
      (node (ref "R9") (pin "2") (pinfunction "2_2") (pintype "passive"))
      (node (ref "SJR1") (pin "11") (pinfunction "GPIO2_11") (pintype "bidirectional"))
    )
    (net (code "41") (name "M+") (class "Default")
      (node (ref "M1") (pin "1") (pinfunction "OA_1") (pintype "bidirectional"))
      (node (ref "PAD18") (pin "1") (pinfunction "P_1") (pintype "passive"))
    )
    (net (code "42") (name "M-") (class "Default")
      (node (ref "M1") (pin "4") (pinfunction "OB_4") (pintype "bidirectional"))
      (node (ref "PAD19") (pin "1") (pinfunction "P_1") (pintype "passive"))
    )
    (net (code "43") (name "NRST") (class "Default")
      (node (ref "R1") (pin "2") (pinfunction "2_2") (pintype "passive"))
      (node (ref "SJR1") (pin "1") (pinfunction "REST_1") (pintype "bidirectional"))
      (node (ref "T1") (pin "C") (pinfunction "C_C") (pintype "passive"))
    )
    (net (code "44") (name "Net-(D1-C)") (class "Default")
      (node (ref "D1") (pin "3") (pinfunction "C_3") (pintype "passive"))
      (node (ref "IC2") (pin "1") (pinfunction "GND_1") (pintype "power_in"))
      (node (ref "R6") (pin "2") (pinfunction "2_2") (pintype "passive"))
    )
    (net (code "45") (name "Net-(IC1-GND)") (class "Default")
      (node (ref "B1") (pin "AC1") (pinfunction "AC1_AC1") (pintype "passive"))
      (node (ref "C2") (pin "1") (pinfunction "1_1") (pintype "passive"))
      (node (ref "IC1") (pin "1") (pinfunction "GND_1") (pintype "power_in"))
      (node (ref "R5") (pin "2") (pinfunction "2_2") (pintype "passive"))
      (node (ref "R8") (pin "2") (pinfunction "2_2") (pintype "passive"))
    )
    (net (code "46") (name "Net-(IC1-VIN)") (class "Default")
      (node (ref "C1") (pin "1") (pinfunction "1_1") (pintype "passive"))
      (node (ref "IC1") (pin "3") (pinfunction "VIN_3") (pintype "input"))
      (node (ref "IC2") (pin "2") (pinfunction "VOUT_2") (pintype "output"))
      (node (ref "R6") (pin "1") (pinfunction "1_1") (pintype "passive"))
    )
    (net (code "47") (name "Net-(IC1-VOUT)") (class "Default")
      (node (ref "IC1") (pin "2") (pinfunction "VOUT_2") (pintype "output"))
      (node (ref "R5") (pin "1") (pinfunction "1_1") (pintype "passive"))
      (node (ref "R8") (pin "1") (pinfunction "1_1") (pintype "passive"))
    )
    (net (code "48") (name "Net-(LED1-PadA)") (class "Default")
      (node (ref "LED1") (pin "A") (pinfunction "A_A") (pintype "passive"))
      (node (ref "R7") (pin "2") (pinfunction "2_2") (pintype "passive"))
    )
    (net (code "49") (name "Net-(LED2-PadA)") (class "Default")
      (node (ref "LED2") (pin "A") (pinfunction "A_A") (pintype "passive"))
      (node (ref "R12") (pin "2") (pinfunction "2_2") (pintype "passive"))
    )
    (net (code "50") (name "Net-(LED3-PadA)") (class "Default")
      (node (ref "LED3") (pin "A") (pinfunction "A_A") (pintype "passive"))
      (node (ref "R22") (pin "2") (pinfunction "2_2") (pintype "passive"))
    )
    (net (code "51") (name "Net-(R10-Pad1)") (class "Default")
      (node (ref "R10") (pin "1") (pinfunction "1_1") (pintype "passive"))
      (node (ref "T1") (pin "B") (pinfunction "B_B") (pintype "passive"))
    )
    (net (code "52") (name "Net-(R13-Pad1)") (class "Default")
      (node (ref "R13") (pin "1") (pinfunction "1_1") (pintype "passive"))
      (node (ref "T2") (pin "B") (pinfunction "B_B") (pintype "passive"))
    )
    (net (code "53") (name "Net-(SJR1-CH_PD)") (class "Default")
      (node (ref "R2") (pin "2") (pinfunction "2_2") (pintype "passive"))
      (node (ref "SJR1") (pin "3") (pinfunction "CH_PD_3") (pintype "bidirectional"))
    )
    (net (code "54") (name "Net-(U$1-RX)") (class "Default")
      (node (ref "R15") (pin "2") (pinfunction "2_2") (pintype "passive"))
      (node (ref "U$1") (pin "3") (pinfunction "RX_3") (pintype "bidirectional"))
    )
    (net (code "55") (name "Net-(U$1-TX)") (class "Default")
      (node (ref "R14") (pin "2") (pinfunction "2_2") (pintype "passive"))
      (node (ref "U$1") (pin "2") (pinfunction "TX_2") (pintype "bidirectional"))
    )
    (net (code "56") (name "Net-(U$1-XI)") (class "Default")
      (node (ref "C5") (pin "1") (pinfunction "1_1") (pintype "passive"))
      (node (ref "Q1") (pin "2") (pinfunction "2_2") (pintype "passive"))
      (node (ref "U$1") (pin "7") (pinfunction "XI_7") (pintype "bidirectional"))
    )
    (net (code "57") (name "Net-(U$1-XO)") (class "Default")
      (node (ref "C4") (pin "1") (pinfunction "1_1") (pintype "passive"))
      (node (ref "Q1") (pin "1") (pinfunction "1_1") (pintype "passive"))
      (node (ref "U$1") (pin "8") (pinfunction "XO_8") (pintype "bidirectional"))
    )
    (net (code "58") (name "Net-(U1-PB6(XTAL1{slash}TOSC1))") (class "Default")
      (node (ref "C8") (pin "1") (pinfunction "1_1") (pintype "passive"))
      (node (ref "Q3") (pin "2") (pinfunction "2_2") (pintype "passive"))
      (node (ref "U1") (pin "7") (pinfunction "PB6(XTAL1/TOSC1)_7") (pintype "bidirectional"))
    )
    (net (code "59") (name "Net-(U1-PB7(XTAL2{slash}TOSC2))") (class "Default")
      (node (ref "C7") (pin "1") (pinfunction "1_1") (pintype "passive"))
      (node (ref "Q3") (pin "1") (pinfunction "1_1") (pintype "passive"))
      (node (ref "U1") (pin "8") (pinfunction "PB7(XTAL2/TOSC2)_8") (pintype "bidirectional"))
    )
    (net (code "60") (name "Net-(U1-PC6({slash}RESET))") (class "Default")
      (node (ref "R11") (pin "1") (pinfunction "1_1") (pintype "passive"))
      (node (ref "U1") (pin "29") (pinfunction "PC6(/RESET)_29") (pintype "bidirectional"))
    )
    (net (code "61") (name "RTS") (class "Default")
      (node (ref "R13") (pin "2") (pinfunction "2_2") (pintype "passive"))
      (node (ref "T1") (pin "E") (pinfunction "E_E") (pintype "passive"))
      (node (ref "U$1") (pin "14") (pinfunction "RTS_14") (pintype "bidirectional"))
    )
    (net (code "62") (name "RX") (class "Default")
      (node (ref "PAD12") (pin "1") (pinfunction "P_1") (pintype "passive"))
      (node (ref "R14") (pin "1") (pinfunction "1_1") (pintype "passive"))
      (node (ref "SJR1") (pin "15") (pinfunction "RXD_15") (pintype "bidirectional"))
    )
    (net (code "63") (name "SCL3") (class "Default")
      (node (ref "PAD15") (pin "1") (pinfunction "P_1") (pintype "passive"))
      (node (ref "Q4") (pin "2") (pinfunction "S_2") (pintype "bidirectional"))
      (node (ref "R16") (pin "1") (pinfunction "1_1") (pintype "passive"))
      (node (ref "SJR1") (pin "14") (pinfunction "GPIO5_14") (pintype "bidirectional"))
    )
    (net (code "64") (name "SCL5") (class "Default")
      (node (ref "PAD27") (pin "1") (pinfunction "P_1") (pintype "passive"))
      (node (ref "Q4") (pin "3") (pinfunction "D_3") (pintype "bidirectional"))
      (node (ref "R17") (pin "2") (pinfunction "2_2") (pintype "passive"))
      (node (ref "U1") (pin "28") (pinfunction "PC5(ADC5/SCL)_28") (pintype "bidirectional"))
    )
    (net (code "65") (name "SDA3") (class "Default")
      (node (ref "PAD14") (pin "1") (pinfunction "P_1") (pintype "passive"))
      (node (ref "Q2") (pin "2") (pinfunction "S_2") (pintype "bidirectional"))
      (node (ref "R18") (pin "1") (pinfunction "1_1") (pintype "passive"))
      (node (ref "SJR1") (pin "13") (pinfunction "GPIO4_13") (pintype "bidirectional"))
    )
    (net (code "66") (name "SDA5") (class "Default")
      (node (ref "PAD26") (pin "1") (pinfunction "P_1") (pintype "passive"))
      (node (ref "Q2") (pin "3") (pinfunction "D_3") (pintype "bidirectional"))
      (node (ref "R19") (pin "2") (pinfunction "2_2") (pintype "passive"))
      (node (ref "U1") (pin "27") (pinfunction "PC4(ADC4/SDA)_27") (pintype "bidirectional"))
    )
    (net (code "67") (name "TX") (class "Default")
      (node (ref "PAD13") (pin "1") (pinfunction "P_1") (pintype "passive"))
      (node (ref "R15") (pin "1") (pinfunction "1_1") (pintype "passive"))
      (node (ref "SJR1") (pin "16") (pinfunction "TXD_16") (pintype "bidirectional"))
    )
    (net (code "68") (name "V3") (class "Default")
      (node (ref "C6") (pin "1") (pinfunction "1_1") (pintype "passive"))
      (node (ref "U$1") (pin "4") (pinfunction "V3_4") (pintype "bidirectional"))
    )
    (net (code "69") (name "VBAT") (class "Default")
      (node (ref "B1") (pin "+") (pinfunction "+_+") (pintype "passive"))
      (node (ref "IC3") (pin "3") (pinfunction "VIN_3") (pintype "input"))
      (node (ref "IC4") (pin "3") (pinfunction "VIN_3") (pintype "input"))
      (node (ref "IC5") (pin "3") (pinfunction "VIN_3") (pintype "input"))
      (node (ref "IC6") (pin "3") (pinfunction "VIN_3") (pintype "input"))
      (node (ref "PAD4") (pin "1") (pinfunction "P_1") (pintype "passive"))
    )
    (net (code "70") (name "VCC") (class "Default")
      (node (ref "C15") (pin "2") (pinfunction "2_2") (pintype "passive"))
      (node (ref "D2") (pin "A") (pinfunction "A_A") (pintype "passive"))
      (node (ref "R12") (pin "1") (pinfunction "1_1") (pintype "passive"))
      (node (ref "U$2") (pin "1") (pinfunction "1_1") (pintype "input"))
    )
    (net (code "71") (name "unconnected-(SJR1-CS0-Pad17)") (class "Default")
      (node (ref "SJR1") (pin "17") (pinfunction "CS0_17") (pintype "bidirectional"))
    )
    (net (code "72") (name "unconnected-(SJR1-GPIO9-Pad19)") (class "Default")
      (node (ref "SJR1") (pin "19") (pinfunction "GPIO9_19") (pintype "bidirectional"))
    )
    (net (code "73") (name "unconnected-(SJR1-GPIO10-Pad20)") (class "Default")
      (node (ref "SJR1") (pin "20") (pinfunction "GPIO10_20") (pintype "bidirectional"))
    )
    (net (code "74") (name "unconnected-(SJR1-MISO-Pad18)") (class "Default")
      (node (ref "SJR1") (pin "18") (pinfunction "MISO_18") (pintype "bidirectional"))
    )
    (net (code "75") (name "unconnected-(SJR1-MOSI-Pad21)") (class "Default")
      (node (ref "SJR1") (pin "21") (pinfunction "MOSI_21") (pintype "bidirectional"))
    )
    (net (code "76") (name "unconnected-(SJR1-SCLK-Pad22)") (class "Default")
      (node (ref "SJR1") (pin "22") (pinfunction "SCLK_22") (pintype "bidirectional"))
    )
    (net (code "77") (name "unconnected-(U$1-CTS-Pad9)") (class "Default")
      (node (ref "U$1") (pin "9") (pinfunction "CTS_9") (pintype "bidirectional"))
    )
    (net (code "78") (name "unconnected-(U$1-DCD-Pad12)") (class "Default")
      (node (ref "U$1") (pin "12") (pinfunction "DCD_12") (pintype "bidirectional"))
    )
    (net (code "79") (name "unconnected-(U$1-DSR-Pad10)") (class "Default")
      (node (ref "U$1") (pin "10") (pinfunction "DSR_10") (pintype "bidirectional"))
    )
    (net (code "80") (name "unconnected-(U$1-RI-Pad11)") (class "Default")
      (node (ref "U$1") (pin "11") (pinfunction "RI_11") (pintype "bidirectional"))
    )
    (net (code "81") (name "unconnected-(U$1-RS232-Pad15)") (class "Default")
      (node (ref "U$1") (pin "15") (pinfunction "RS232_15") (pintype "bidirectional"))
    )
    (net (code "82") (name "unconnected-(U$2-GND1-PadP$1)") (class "Default")
      (node (ref "U$2") (pin "P$1") (pinfunction "GND1_P$1") (pintype "bidirectional"))
    )
    (net (code "83") (name "unconnected-(U$2-Pad4)") (class "Default")
      (node (ref "U$2") (pin "4") (pinfunction "4_4") (pintype "input"))
    )
    (net (code "84") (name "unconnected-(U1-AREF-Pad20)") (class "Default")
      (node (ref "U1") (pin "20") (pinfunction "AREF_20") (pintype "bidirectional"))
    )
  )
)
